# LEDS2.net
KiCad netlist of a schematic drawn in Altium Designer
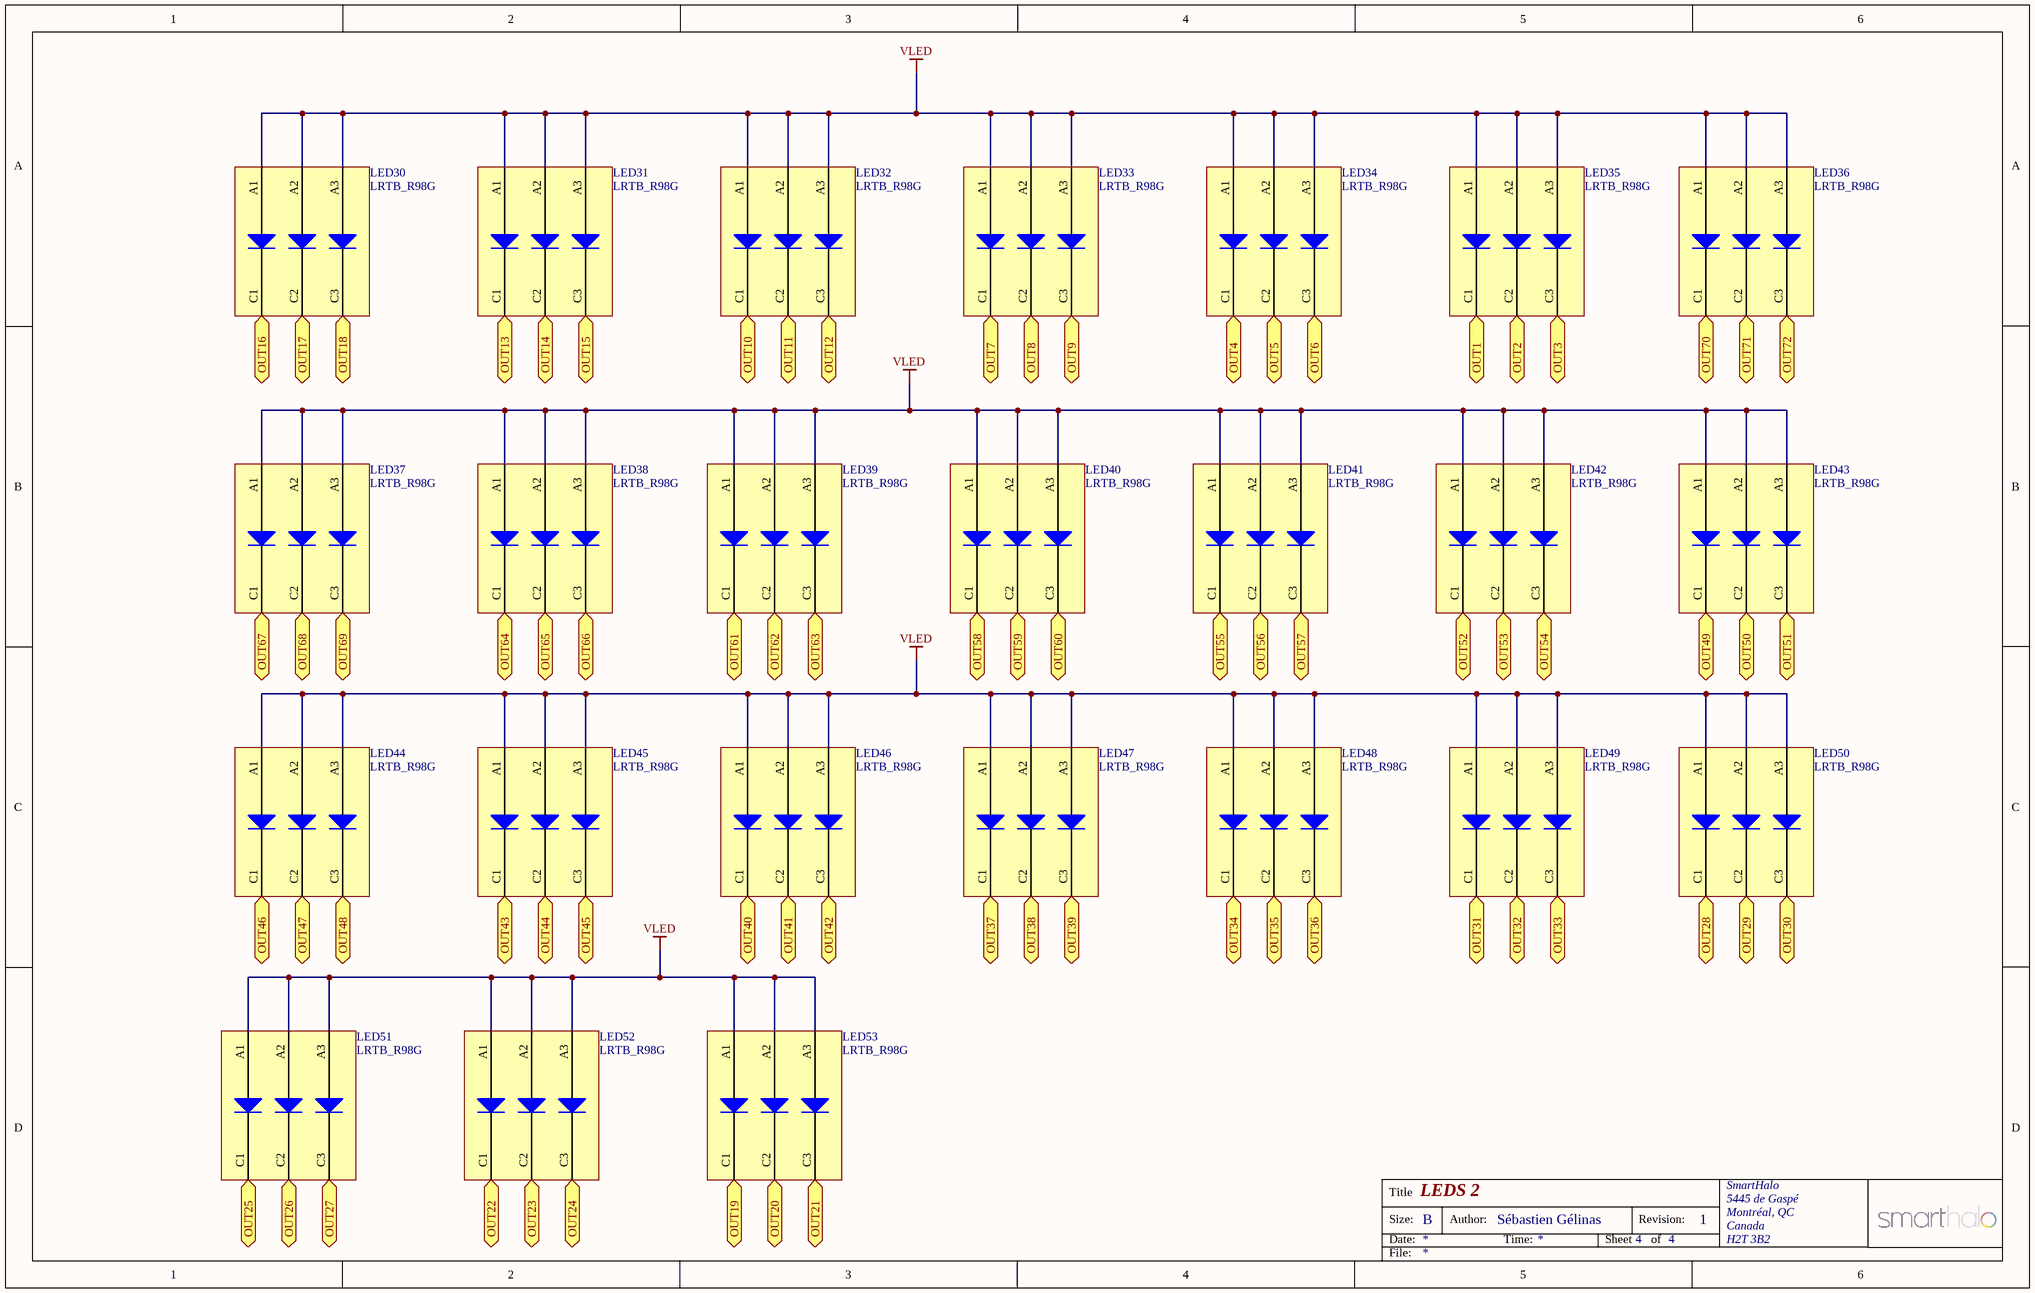
[diagram p0: LEDS2.SchDoc]

(export (version "E")
  (design (tool "Eeschema 10.0.6"))
  (components
    (comp (ref "LED30")
      (value "LRTB_R98G")
      (footprint "LRTB_R98G")
      (description "IC RGB LED OSRAM")
      (fields (field (name "MANUFACTURER") "OSRAM"))
      (libsource (lib "SmartHalo_Symbols") (part "LRTB_R98G"))
    )
    (comp (ref "LED31")
      (value "LRTB_R98G")
      (footprint "LRTB_R98G")
      (description "IC RGB LED OSRAM")
      (fields (field (name "MANUFACTURER") "OSRAM"))
      (libsource (lib "SmartHalo_Symbols") (part "LRTB_R98G"))
    )
    (comp (ref "LED32")
      (value "LRTB_R98G")
      (footprint "LRTB_R98G")
      (description "IC RGB LED OSRAM")
      (fields (field (name "MANUFACTURER") "OSRAM"))
      (libsource (lib "SmartHalo_Symbols") (part "LRTB_R98G"))
    )
    (comp (ref "LED33")
      (value "LRTB_R98G")
      (footprint "LRTB_R98G")
      (description "IC RGB LED OSRAM")
      (fields (field (name "MANUFACTURER") "OSRAM"))
      (libsource (lib "SmartHalo_Symbols") (part "LRTB_R98G"))
    )
    (comp (ref "LED34")
      (value "LRTB_R98G")
      (footprint "LRTB_R98G")
      (description "IC RGB LED OSRAM")
      (fields (field (name "MANUFACTURER") "OSRAM"))
      (libsource (lib "SmartHalo_Symbols") (part "LRTB_R98G"))
    )
    (comp (ref "LED35")
      (value "LRTB_R98G")
      (footprint "LRTB_R98G")
      (description "IC RGB LED OSRAM")
      (fields (field (name "MANUFACTURER") "OSRAM"))
      (libsource (lib "SmartHalo_Symbols") (part "LRTB_R98G"))
    )
    (comp (ref "LED36")
      (value "LRTB_R98G")
      (footprint "LRTB_R98G")
      (description "IC RGB LED OSRAM")
      (fields (field (name "MANUFACTURER") "OSRAM"))
      (libsource (lib "SmartHalo_Symbols") (part "LRTB_R98G"))
    )
    (comp (ref "LED37")
      (value "LRTB_R98G")
      (footprint "LRTB_R98G")
      (description "IC RGB LED OSRAM")
      (fields (field (name "MANUFACTURER") "OSRAM"))
      (libsource (lib "SmartHalo_Symbols") (part "LRTB_R98G"))
    )
    (comp (ref "LED38")
      (value "LRTB_R98G")
      (footprint "LRTB_R98G")
      (description "IC RGB LED OSRAM")
      (fields (field (name "MANUFACTURER") "OSRAM"))
      (libsource (lib "SmartHalo_Symbols") (part "LRTB_R98G"))
    )
    (comp (ref "LED39")
      (value "LRTB_R98G")
      (footprint "LRTB_R98G")
      (description "IC RGB LED OSRAM")
      (fields (field (name "MANUFACTURER") "OSRAM"))
      (libsource (lib "SmartHalo_Symbols") (part "LRTB_R98G"))
    )
    (comp (ref "LED40")
      (value "LRTB_R98G")
      (footprint "LRTB_R98G")
      (description "IC RGB LED OSRAM")
      (fields (field (name "MANUFACTURER") "OSRAM"))
      (libsource (lib "SmartHalo_Symbols") (part "LRTB_R98G"))
    )
    (comp (ref "LED41")
      (value "LRTB_R98G")
      (footprint "LRTB_R98G")
      (description "IC RGB LED OSRAM")
      (fields (field (name "MANUFACTURER") "OSRAM"))
      (libsource (lib "SmartHalo_Symbols") (part "LRTB_R98G"))
    )
    (comp (ref "LED42")
      (value "LRTB_R98G")
      (footprint "LRTB_R98G")
      (description "IC RGB LED OSRAM")
      (fields (field (name "MANUFACTURER") "OSRAM"))
      (libsource (lib "SmartHalo_Symbols") (part "LRTB_R98G"))
    )
    (comp (ref "LED43")
      (value "LRTB_R98G")
      (footprint "LRTB_R98G")
      (description "IC RGB LED OSRAM")
      (fields (field (name "MANUFACTURER") "OSRAM"))
      (libsource (lib "SmartHalo_Symbols") (part "LRTB_R98G"))
    )
    (comp (ref "LED44")
      (value "LRTB_R98G")
      (footprint "LRTB_R98G")
      (description "IC RGB LED OSRAM")
      (fields (field (name "MANUFACTURER") "OSRAM"))
      (libsource (lib "SmartHalo_Symbols") (part "LRTB_R98G"))
    )
    (comp (ref "LED45")
      (value "LRTB_R98G")
      (footprint "LRTB_R98G")
      (description "IC RGB LED OSRAM")
      (fields (field (name "MANUFACTURER") "OSRAM"))
      (libsource (lib "SmartHalo_Symbols") (part "LRTB_R98G"))
    )
    (comp (ref "LED46")
      (value "LRTB_R98G")
      (footprint "LRTB_R98G")
      (description "IC RGB LED OSRAM")
      (fields (field (name "MANUFACTURER") "OSRAM"))
      (libsource (lib "SmartHalo_Symbols") (part "LRTB_R98G"))
    )
    (comp (ref "LED47")
      (value "LRTB_R98G")
      (footprint "LRTB_R98G")
      (description "IC RGB LED OSRAM")
      (fields (field (name "MANUFACTURER") "OSRAM"))
      (libsource (lib "SmartHalo_Symbols") (part "LRTB_R98G"))
    )
    (comp (ref "LED48")
      (value "LRTB_R98G")
      (footprint "LRTB_R98G")
      (description "IC RGB LED OSRAM")
      (fields (field (name "MANUFACTURER") "OSRAM"))
      (libsource (lib "SmartHalo_Symbols") (part "LRTB_R98G"))
    )
    (comp (ref "LED49")
      (value "LRTB_R98G")
      (footprint "LRTB_R98G")
      (description "IC RGB LED OSRAM")
      (fields (field (name "MANUFACTURER") "OSRAM"))
      (libsource (lib "SmartHalo_Symbols") (part "LRTB_R98G"))
    )
    (comp (ref "LED50")
      (value "LRTB_R98G")
      (footprint "LRTB_R98G")
      (description "IC RGB LED OSRAM")
      (fields (field (name "MANUFACTURER") "OSRAM"))
      (libsource (lib "SmartHalo_Symbols") (part "LRTB_R98G"))
    )
    (comp (ref "LED51")
      (value "LRTB_R98G")
      (footprint "LRTB_R98G")
      (description "IC RGB LED OSRAM")
      (fields (field (name "MANUFACTURER") "OSRAM"))
      (libsource (lib "SmartHalo_Symbols") (part "LRTB_R98G"))
    )
    (comp (ref "LED52")
      (value "LRTB_R98G")
      (footprint "LRTB_R98G")
      (description "IC RGB LED OSRAM")
      (fields (field (name "MANUFACTURER") "OSRAM"))
      (libsource (lib "SmartHalo_Symbols") (part "LRTB_R98G"))
    )
    (comp (ref "LED53")
      (value "LRTB_R98G")
      (footprint "LRTB_R98G")
      (description "IC RGB LED OSRAM")
      (fields (field (name "MANUFACTURER") "OSRAM"))
      (libsource (lib "SmartHalo_Symbols") (part "LRTB_R98G"))
    )
  )
  (nets
    (net (code "1") (name "/OUT1") (class "Default")
      (node (ref "LED35") (pin "C1") (pinfunction "Cathode_Blue_C1") (pintype "passive"))
    )
    (net (code "2") (name "/OUT2") (class "Default")
      (node (ref "LED35") (pin "C2") (pinfunction "Cathode_Green_C2") (pintype "passive"))
    )
    (net (code "3") (name "/OUT3") (class "Default")
      (node (ref "LED35") (pin "C3") (pinfunction "Cathode_Red_C3") (pintype "passive"))
    )
    (net (code "4") (name "/OUT4") (class "Default")
      (node (ref "LED34") (pin "C1") (pinfunction "Cathode_Blue_C1") (pintype "passive"))
    )
    (net (code "5") (name "/OUT5") (class "Default")
      (node (ref "LED34") (pin "C2") (pinfunction "Cathode_Green_C2") (pintype "passive"))
    )
    (net (code "6") (name "/OUT6") (class "Default")
      (node (ref "LED34") (pin "C3") (pinfunction "Cathode_Red_C3") (pintype "passive"))
    )
    (net (code "7") (name "/OUT7") (class "Default")
      (node (ref "LED33") (pin "C1") (pinfunction "Cathode_Blue_C1") (pintype "passive"))
    )
    (net (code "8") (name "/OUT8") (class "Default")
      (node (ref "LED33") (pin "C2") (pinfunction "Cathode_Green_C2") (pintype "passive"))
    )
    (net (code "9") (name "/OUT9") (class "Default")
      (node (ref "LED33") (pin "C3") (pinfunction "Cathode_Red_C3") (pintype "passive"))
    )
    (net (code "10") (name "/OUT10") (class "Default")
      (node (ref "LED32") (pin "C1") (pinfunction "Cathode_Blue_C1") (pintype "passive"))
    )
    (net (code "11") (name "/OUT11") (class "Default")
      (node (ref "LED32") (pin "C2") (pinfunction "Cathode_Green_C2") (pintype "passive"))
    )
    (net (code "12") (name "/OUT12") (class "Default")
      (node (ref "LED32") (pin "C3") (pinfunction "Cathode_Red_C3") (pintype "passive"))
    )
    (net (code "13") (name "/OUT13") (class "Default")
      (node (ref "LED31") (pin "C1") (pinfunction "Cathode_Blue_C1") (pintype "passive"))
    )
    (net (code "14") (name "/OUT14") (class "Default")
      (node (ref "LED31") (pin "C2") (pinfunction "Cathode_Green_C2") (pintype "passive"))
    )
    (net (code "15") (name "/OUT15") (class "Default")
      (node (ref "LED31") (pin "C3") (pinfunction "Cathode_Red_C3") (pintype "passive"))
    )
    (net (code "16") (name "/OUT16") (class "Default")
      (node (ref "LED30") (pin "C1") (pinfunction "Cathode_Blue_C1") (pintype "passive"))
    )
    (net (code "17") (name "/OUT17") (class "Default")
      (node (ref "LED30") (pin "C2") (pinfunction "Cathode_Green_C2") (pintype "passive"))
    )
    (net (code "18") (name "/OUT18") (class "Default")
      (node (ref "LED30") (pin "C3") (pinfunction "Cathode_Red_C3") (pintype "passive"))
    )
    (net (code "19") (name "/OUT19") (class "Default")
      (node (ref "LED53") (pin "C1") (pinfunction "Cathode_Blue_C1") (pintype "passive"))
    )
    (net (code "20") (name "/OUT20") (class "Default")
      (node (ref "LED53") (pin "C2") (pinfunction "Cathode_Green_C2") (pintype "passive"))
    )
    (net (code "21") (name "/OUT21") (class "Default")
      (node (ref "LED53") (pin "C3") (pinfunction "Cathode_Red_C3") (pintype "passive"))
    )
    (net (code "22") (name "/OUT22") (class "Default")
      (node (ref "LED52") (pin "C1") (pinfunction "Cathode_Blue_C1") (pintype "passive"))
    )
    (net (code "23") (name "/OUT23") (class "Default")
      (node (ref "LED52") (pin "C2") (pinfunction "Cathode_Green_C2") (pintype "passive"))
    )
    (net (code "24") (name "/OUT24") (class "Default")
      (node (ref "LED52") (pin "C3") (pinfunction "Cathode_Red_C3") (pintype "passive"))
    )
    (net (code "25") (name "/OUT25") (class "Default")
      (node (ref "LED51") (pin "C1") (pinfunction "Cathode_Blue_C1") (pintype "passive"))
    )
    (net (code "26") (name "/OUT26") (class "Default")
      (node (ref "LED51") (pin "C2") (pinfunction "Cathode_Green_C2") (pintype "passive"))
    )
    (net (code "27") (name "/OUT27") (class "Default")
      (node (ref "LED51") (pin "C3") (pinfunction "Cathode_Red_C3") (pintype "passive"))
    )
    (net (code "28") (name "/OUT28") (class "Default")
      (node (ref "LED50") (pin "C1") (pinfunction "Cathode_Blue_C1") (pintype "passive"))
    )
    (net (code "29") (name "/OUT29") (class "Default")
      (node (ref "LED50") (pin "C2") (pinfunction "Cathode_Green_C2") (pintype "passive"))
    )
    (net (code "30") (name "/OUT30") (class "Default")
      (node (ref "LED50") (pin "C3") (pinfunction "Cathode_Red_C3") (pintype "passive"))
    )
    (net (code "31") (name "/OUT31") (class "Default")
      (node (ref "LED49") (pin "C1") (pinfunction "Cathode_Blue_C1") (pintype "passive"))
    )
    (net (code "32") (name "/OUT32") (class "Default")
      (node (ref "LED49") (pin "C2") (pinfunction "Cathode_Green_C2") (pintype "passive"))
    )
    (net (code "33") (name "/OUT33") (class "Default")
      (node (ref "LED49") (pin "C3") (pinfunction "Cathode_Red_C3") (pintype "passive"))
    )
    (net (code "34") (name "/OUT34") (class "Default")
      (node (ref "LED48") (pin "C1") (pinfunction "Cathode_Blue_C1") (pintype "passive"))
    )
    (net (code "35") (name "/OUT35") (class "Default")
      (node (ref "LED48") (pin "C2") (pinfunction "Cathode_Green_C2") (pintype "passive"))
    )
    (net (code "36") (name "/OUT36") (class "Default")
      (node (ref "LED48") (pin "C3") (pinfunction "Cathode_Red_C3") (pintype "passive"))
    )
    (net (code "37") (name "/OUT37") (class "Default")
      (node (ref "LED47") (pin "C1") (pinfunction "Cathode_Blue_C1") (pintype "passive"))
    )
    (net (code "38") (name "/OUT38") (class "Default")
      (node (ref "LED47") (pin "C2") (pinfunction "Cathode_Green_C2") (pintype "passive"))
    )
    (net (code "39") (name "/OUT39") (class "Default")
      (node (ref "LED47") (pin "C3") (pinfunction "Cathode_Red_C3") (pintype "passive"))
    )
    (net (code "40") (name "/OUT40") (class "Default")
      (node (ref "LED46") (pin "C1") (pinfunction "Cathode_Blue_C1") (pintype "passive"))
    )
    (net (code "41") (name "/OUT41") (class "Default")
      (node (ref "LED46") (pin "C2") (pinfunction "Cathode_Green_C2") (pintype "passive"))
    )
    (net (code "42") (name "/OUT42") (class "Default")
      (node (ref "LED46") (pin "C3") (pinfunction "Cathode_Red_C3") (pintype "passive"))
    )
    (net (code "43") (name "/OUT43") (class "Default")
      (node (ref "LED45") (pin "C1") (pinfunction "Cathode_Blue_C1") (pintype "passive"))
    )
    (net (code "44") (name "/OUT44") (class "Default")
      (node (ref "LED45") (pin "C2") (pinfunction "Cathode_Green_C2") (pintype "passive"))
    )
    (net (code "45") (name "/OUT45") (class "Default")
      (node (ref "LED45") (pin "C3") (pinfunction "Cathode_Red_C3") (pintype "passive"))
    )
    (net (code "46") (name "/OUT46") (class "Default")
      (node (ref "LED44") (pin "C1") (pinfunction "Cathode_Blue_C1") (pintype "passive"))
    )
    (net (code "47") (name "/OUT47") (class "Default")
      (node (ref "LED44") (pin "C2") (pinfunction "Cathode_Green_C2") (pintype "passive"))
    )
    (net (code "48") (name "/OUT48") (class "Default")
      (node (ref "LED44") (pin "C3") (pinfunction "Cathode_Red_C3") (pintype "passive"))
    )
    (net (code "49") (name "/OUT49") (class "Default")
      (node (ref "LED43") (pin "C1") (pinfunction "Cathode_Blue_C1") (pintype "passive"))
    )
    (net (code "50") (name "/OUT50") (class "Default")
      (node (ref "LED43") (pin "C2") (pinfunction "Cathode_Green_C2") (pintype "passive"))
    )
    (net (code "51") (name "/OUT51") (class "Default")
      (node (ref "LED43") (pin "C3") (pinfunction "Cathode_Red_C3") (pintype "passive"))
    )
    (net (code "52") (name "/OUT52") (class "Default")
      (node (ref "LED42") (pin "C1") (pinfunction "Cathode_Blue_C1") (pintype "passive"))
    )
    (net (code "53") (name "/OUT53") (class "Default")
      (node (ref "LED42") (pin "C2") (pinfunction "Cathode_Green_C2") (pintype "passive"))
    )
    (net (code "54") (name "/OUT54") (class "Default")
      (node (ref "LED42") (pin "C3") (pinfunction "Cathode_Red_C3") (pintype "passive"))
    )
    (net (code "55") (name "/OUT55") (class "Default")
      (node (ref "LED41") (pin "C1") (pinfunction "Cathode_Blue_C1") (pintype "passive"))
    )
    (net (code "56") (name "/OUT56") (class "Default")
      (node (ref "LED41") (pin "C2") (pinfunction "Cathode_Green_C2") (pintype "passive"))
    )
    (net (code "57") (name "/OUT57") (class "Default")
      (node (ref "LED41") (pin "C3") (pinfunction "Cathode_Red_C3") (pintype "passive"))
    )
    (net (code "58") (name "/OUT58") (class "Default")
      (node (ref "LED40") (pin "C1") (pinfunction "Cathode_Blue_C1") (pintype "passive"))
    )
    (net (code "59") (name "/OUT59") (class "Default")
      (node (ref "LED40") (pin "C2") (pinfunction "Cathode_Green_C2") (pintype "passive"))
    )
    (net (code "60") (name "/OUT60") (class "Default")
      (node (ref "LED40") (pin "C3") (pinfunction "Cathode_Red_C3") (pintype "passive"))
    )
    (net (code "61") (name "/OUT61") (class "Default")
      (node (ref "LED39") (pin "C1") (pinfunction "Cathode_Blue_C1") (pintype "passive"))
    )
    (net (code "62") (name "/OUT62") (class "Default")
      (node (ref "LED39") (pin "C2") (pinfunction "Cathode_Green_C2") (pintype "passive"))
    )
    (net (code "63") (name "/OUT63") (class "Default")
      (node (ref "LED39") (pin "C3") (pinfunction "Cathode_Red_C3") (pintype "passive"))
    )
    (net (code "64") (name "/OUT64") (class "Default")
      (node (ref "LED38") (pin "C1") (pinfunction "Cathode_Blue_C1") (pintype "passive"))
    )
    (net (code "65") (name "/OUT65") (class "Default")
      (node (ref "LED38") (pin "C2") (pinfunction "Cathode_Green_C2") (pintype "passive"))
    )
    (net (code "66") (name "/OUT66") (class "Default")
      (node (ref "LED38") (pin "C3") (pinfunction "Cathode_Red_C3") (pintype "passive"))
    )
    (net (code "67") (name "/OUT67") (class "Default")
      (node (ref "LED37") (pin "C1") (pinfunction "Cathode_Blue_C1") (pintype "passive"))
    )
    (net (code "68") (name "/OUT68") (class "Default")
      (node (ref "LED37") (pin "C2") (pinfunction "Cathode_Green_C2") (pintype "passive"))
    )
    (net (code "69") (name "/OUT69") (class "Default")
      (node (ref "LED37") (pin "C3") (pinfunction "Cathode_Red_C3") (pintype "passive"))
    )
    (net (code "70") (name "/OUT70") (class "Default")
      (node (ref "LED36") (pin "C1") (pinfunction "Cathode_Blue_C1") (pintype "passive"))
    )
    (net (code "71") (name "/OUT71") (class "Default")
      (node (ref "LED36") (pin "C2") (pinfunction "Cathode_Green_C2") (pintype "passive"))
    )
    (net (code "72") (name "/OUT72") (class "Default")
      (node (ref "LED36") (pin "C3") (pinfunction "Cathode_Red_C3") (pintype "passive"))
    )
    (net (code "73") (name "VLED") (class "Default")
      (node (ref "LED30") (pin "A1") (pinfunction "Anode_Blue_A1") (pintype "passive"))
      (node (ref "LED30") (pin "A2") (pinfunction "Anode_Green_A2") (pintype "passive"))
      (node (ref "LED30") (pin "A3") (pinfunction "Anode_Red_A3") (pintype "passive"))
      (node (ref "LED31") (pin "A1") (pinfunction "Anode_Blue_A1") (pintype "passive"))
      (node (ref "LED31") (pin "A2") (pinfunction "Anode_Green_A2") (pintype "passive"))
      (node (ref "LED31") (pin "A3") (pinfunction "Anode_Red_A3") (pintype "passive"))
      (node (ref "LED32") (pin "A1") (pinfunction "Anode_Blue_A1") (pintype "passive"))
      (node (ref "LED32") (pin "A2") (pinfunction "Anode_Green_A2") (pintype "passive"))
      (node (ref "LED32") (pin "A3") (pinfunction "Anode_Red_A3") (pintype "passive"))
      (node (ref "LED33") (pin "A1") (pinfunction "Anode_Blue_A1") (pintype "passive"))
      (node (ref "LED33") (pin "A2") (pinfunction "Anode_Green_A2") (pintype "passive"))
      (node (ref "LED33") (pin "A3") (pinfunction "Anode_Red_A3") (pintype "passive"))
      (node (ref "LED34") (pin "A1") (pinfunction "Anode_Blue_A1") (pintype "passive"))
      (node (ref "LED34") (pin "A2") (pinfunction "Anode_Green_A2") (pintype "passive"))
      (node (ref "LED34") (pin "A3") (pinfunction "Anode_Red_A3") (pintype "passive"))
      (node (ref "LED35") (pin "A1") (pinfunction "Anode_Blue_A1") (pintype "passive"))
      (node (ref "LED35") (pin "A2") (pinfunction "Anode_Green_A2") (pintype "passive"))
      (node (ref "LED35") (pin "A3") (pinfunction "Anode_Red_A3") (pintype "passive"))
      (node (ref "LED36") (pin "A1") (pinfunction "Anode_Blue_A1") (pintype "passive"))
      (node (ref "LED36") (pin "A2") (pinfunction "Anode_Green_A2") (pintype "passive"))
      (node (ref "LED36") (pin "A3") (pinfunction "Anode_Red_A3") (pintype "passive"))
      (node (ref "LED37") (pin "A1") (pinfunction "Anode_Blue_A1") (pintype "passive"))
      (node (ref "LED37") (pin "A2") (pinfunction "Anode_Green_A2") (pintype "passive"))
      (node (ref "LED37") (pin "A3") (pinfunction "Anode_Red_A3") (pintype "passive"))
      (node (ref "LED38") (pin "A1") (pinfunction "Anode_Blue_A1") (pintype "passive"))
      (node (ref "LED38") (pin "A2") (pinfunction "Anode_Green_A2") (pintype "passive"))
      (node (ref "LED38") (pin "A3") (pinfunction "Anode_Red_A3") (pintype "passive"))
      (node (ref "LED39") (pin "A1") (pinfunction "Anode_Blue_A1") (pintype "passive"))
      (node (ref "LED39") (pin "A2") (pinfunction "Anode_Green_A2") (pintype "passive"))
      (node (ref "LED39") (pin "A3") (pinfunction "Anode_Red_A3") (pintype "passive"))
      (node (ref "LED40") (pin "A1") (pinfunction "Anode_Blue_A1") (pintype "passive"))
      (node (ref "LED40") (pin "A2") (pinfunction "Anode_Green_A2") (pintype "passive"))
      (node (ref "LED40") (pin "A3") (pinfunction "Anode_Red_A3") (pintype "passive"))
      (node (ref "LED41") (pin "A1") (pinfunction "Anode_Blue_A1") (pintype "passive"))
      (node (ref "LED41") (pin "A2") (pinfunction "Anode_Green_A2") (pintype "passive"))
      (node (ref "LED41") (pin "A3") (pinfunction "Anode_Red_A3") (pintype "passive"))
      (node (ref "LED42") (pin "A1") (pinfunction "Anode_Blue_A1") (pintype "passive"))
      (node (ref "LED42") (pin "A2") (pinfunction "Anode_Green_A2") (pintype "passive"))
      (node (ref "LED42") (pin "A3") (pinfunction "Anode_Red_A3") (pintype "passive"))
      (node (ref "LED43") (pin "A1") (pinfunction "Anode_Blue_A1") (pintype "passive"))
      (node (ref "LED43") (pin "A2") (pinfunction "Anode_Green_A2") (pintype "passive"))
      (node (ref "LED43") (pin "A3") (pinfunction "Anode_Red_A3") (pintype "passive"))
      (node (ref "LED44") (pin "A1") (pinfunction "Anode_Blue_A1") (pintype "passive"))
      (node (ref "LED44") (pin "A2") (pinfunction "Anode_Green_A2") (pintype "passive"))
      (node (ref "LED44") (pin "A3") (pinfunction "Anode_Red_A3") (pintype "passive"))
      (node (ref "LED45") (pin "A1") (pinfunction "Anode_Blue_A1") (pintype "passive"))
      (node (ref "LED45") (pin "A2") (pinfunction "Anode_Green_A2") (pintype "passive"))
      (node (ref "LED45") (pin "A3") (pinfunction "Anode_Red_A3") (pintype "passive"))
      (node (ref "LED46") (pin "A1") (pinfunction "Anode_Blue_A1") (pintype "passive"))
      (node (ref "LED46") (pin "A2") (pinfunction "Anode_Green_A2") (pintype "passive"))
      (node (ref "LED46") (pin "A3") (pinfunction "Anode_Red_A3") (pintype "passive"))
      (node (ref "LED47") (pin "A1") (pinfunction "Anode_Blue_A1") (pintype "passive"))
      (node (ref "LED47") (pin "A2") (pinfunction "Anode_Green_A2") (pintype "passive"))
      (node (ref "LED47") (pin "A3") (pinfunction "Anode_Red_A3") (pintype "passive"))
      (node (ref "LED48") (pin "A1") (pinfunction "Anode_Blue_A1") (pintype "passive"))
      (node (ref "LED48") (pin "A2") (pinfunction "Anode_Green_A2") (pintype "passive"))
      (node (ref "LED48") (pin "A3") (pinfunction "Anode_Red_A3") (pintype "passive"))
      (node (ref "LED49") (pin "A1") (pinfunction "Anode_Blue_A1") (pintype "passive"))
      (node (ref "LED49") (pin "A2") (pinfunction "Anode_Green_A2") (pintype "passive"))
      (node (ref "LED49") (pin "A3") (pinfunction "Anode_Red_A3") (pintype "passive"))
      (node (ref "LED50") (pin "A1") (pinfunction "Anode_Blue_A1") (pintype "passive"))
      (node (ref "LED50") (pin "A2") (pinfunction "Anode_Green_A2") (pintype "passive"))
      (node (ref "LED50") (pin "A3") (pinfunction "Anode_Red_A3") (pintype "passive"))
      (node (ref "LED51") (pin "A1") (pinfunction "Anode_Blue_A1") (pintype "passive"))
      (node (ref "LED51") (pin "A2") (pinfunction "Anode_Green_A2") (pintype "passive"))
      (node (ref "LED51") (pin "A3") (pinfunction "Anode_Red_A3") (pintype "passive"))
      (node (ref "LED52") (pin "A1") (pinfunction "Anode_Blue_A1") (pintype "passive"))
      (node (ref "LED52") (pin "A2") (pinfunction "Anode_Green_A2") (pintype "passive"))
      (node (ref "LED52") (pin "A3") (pinfunction "Anode_Red_A3") (pintype "passive"))
      (node (ref "LED53") (pin "A1") (pinfunction "Anode_Blue_A1") (pintype "passive"))
      (node (ref "LED53") (pin "A2") (pinfunction "Anode_Green_A2") (pintype "passive"))
      (node (ref "LED53") (pin "A3") (pinfunction "Anode_Red_A3") (pintype "passive"))
    )
  )
)
